# esc_shield.net
KiCad netlist of a schematic drawn in EAGLE
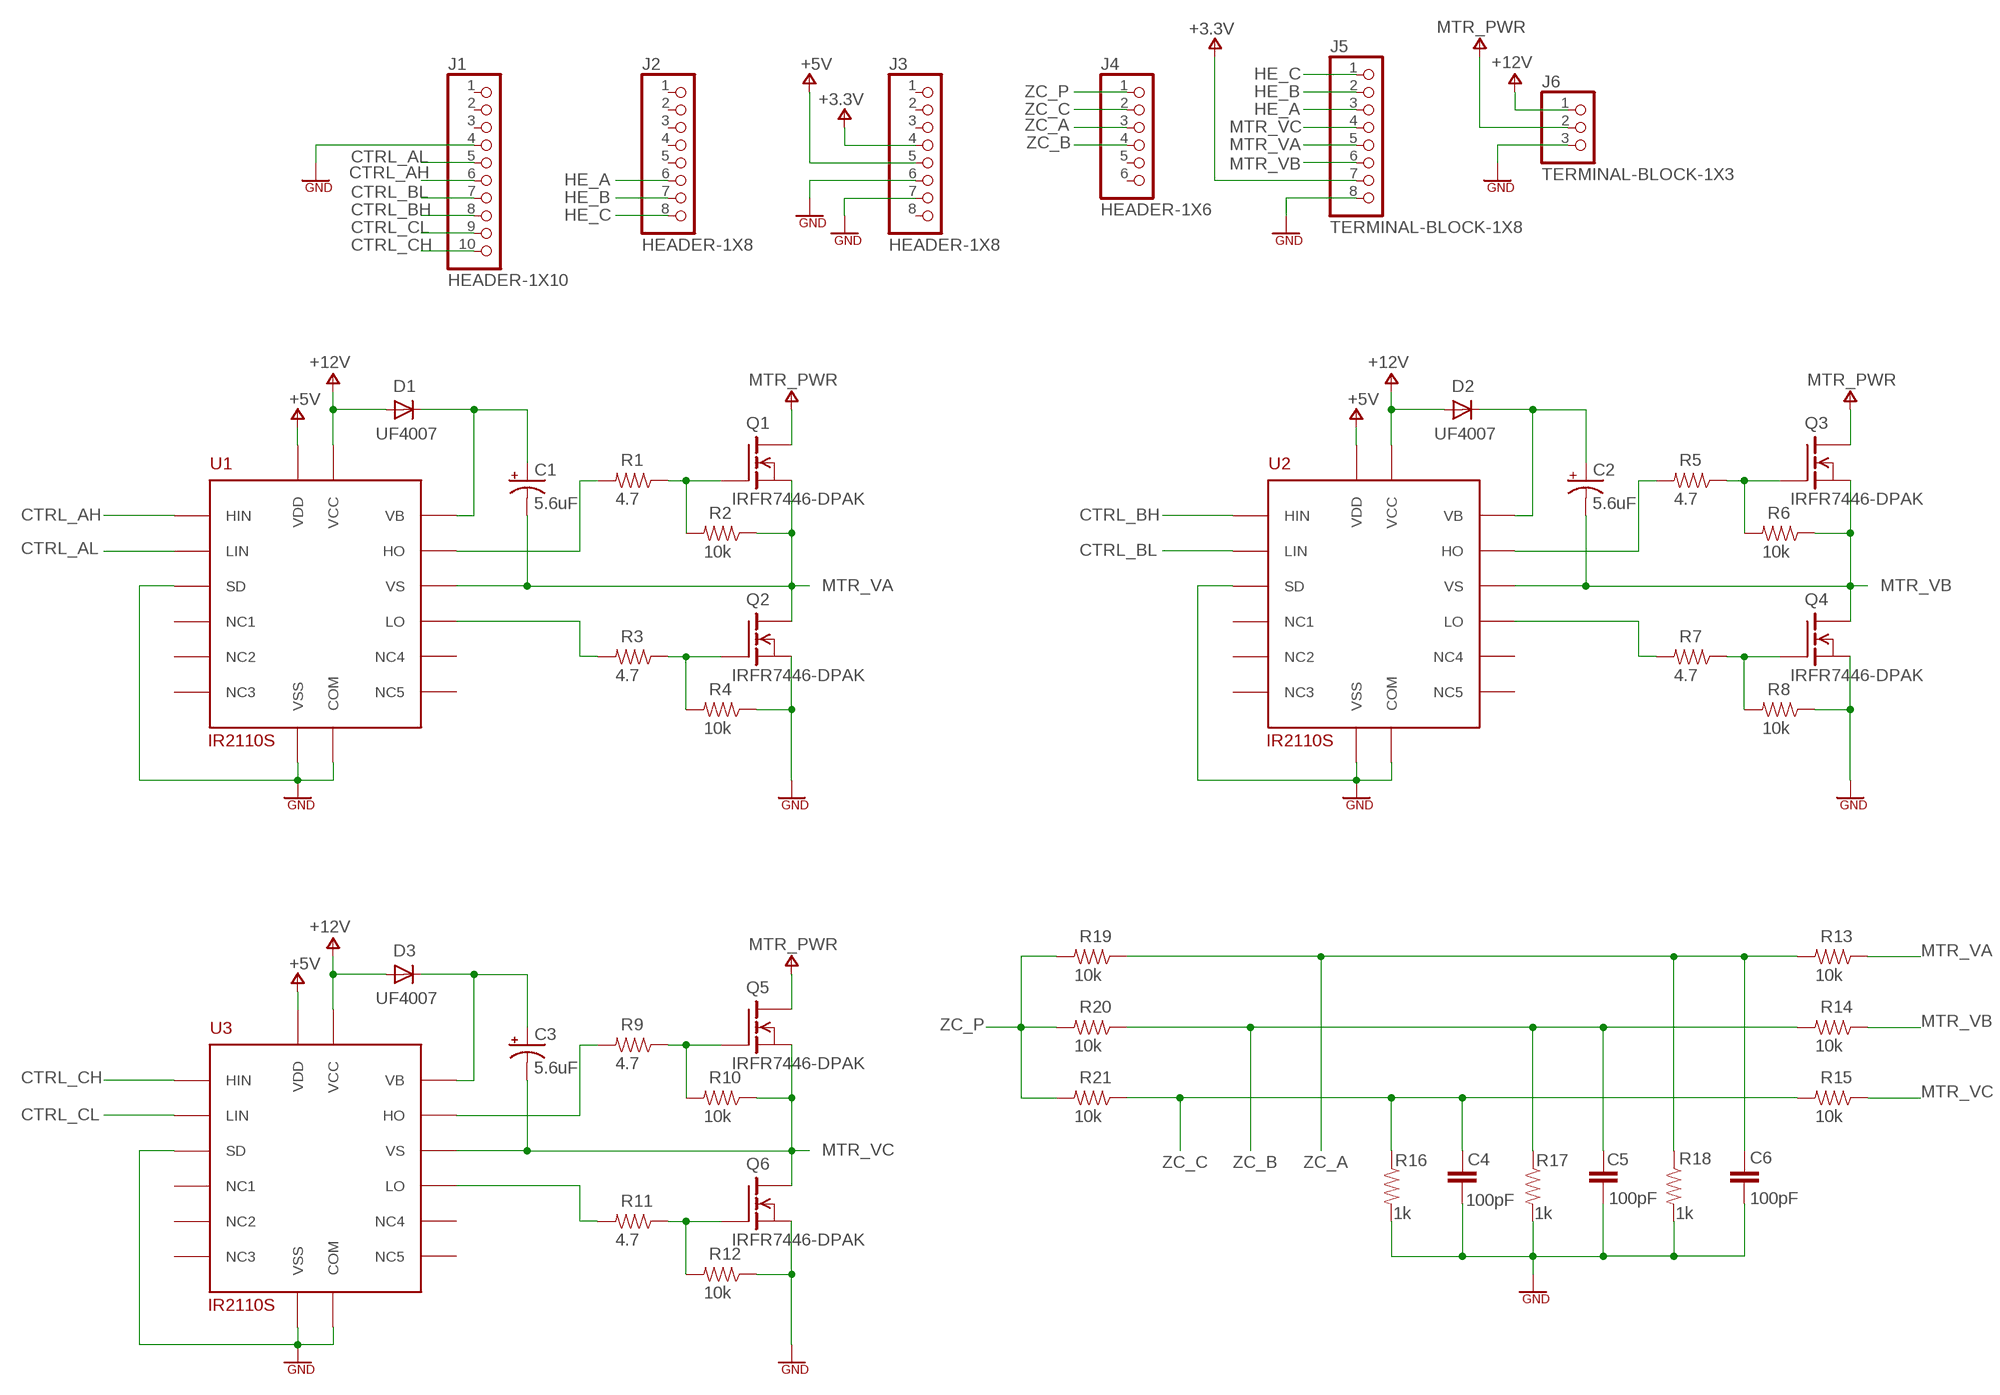
[diagram p0: schematic, sheet 1]

(export (version "E")
  (design (tool "Eeschema 10.0.6"))
  (components
    (comp (ref "C1")
      (value "5.6uF")
      (footprint "eagle-import:EIA7343-31")
      (libsource (lib "eagle-import") (part "CAP_TANT"))
    )
    (comp (ref "C2")
      (value "5.6uF")
      (footprint "eagle-import:EIA7343-31")
      (libsource (lib "eagle-import") (part "CAP_TANT"))
    )
    (comp (ref "C3")
      (value "5.6uF")
      (footprint "eagle-import:EIA7343-31")
      (libsource (lib "eagle-import") (part "CAP_TANT"))
    )
    (comp (ref "C4")
      (value "100pF")
      (footprint "eagle-import:SMD0603")
      (libsource (lib "eagle-import") (part "CAP_0603"))
    )
    (comp (ref "C5")
      (value "100pF")
      (footprint "eagle-import:SMD0603")
      (libsource (lib "eagle-import") (part "CAP_0603"))
    )
    (comp (ref "C6")
      (value "100pF")
      (footprint "eagle-import:SMD0603")
      (libsource (lib "eagle-import") (part "CAP_0603"))
    )
    (comp (ref "D1")
      (value "UF4007")
      (footprint "eagle-import:DO41-10")
      (libsource (lib "eagle-import") (part "UF4007"))
    )
    (comp (ref "D2")
      (value "UF4007")
      (footprint "eagle-import:DO41-10")
      (libsource (lib "eagle-import") (part "UF4007"))
    )
    (comp (ref "D3")
      (value "UF4007")
      (footprint "eagle-import:DO41-10")
      (libsource (lib "eagle-import") (part "UF4007"))
    )
    (comp (ref "J1")
      (value "HEADER-1X10")
      (footprint "eagle-import:1X10")
      (libsource (lib "eagle-import") (part "HEADER-1X10"))
    )
    (comp (ref "J2")
      (value "HEADER-1X8")
      (footprint "eagle-import:1X08")
      (libsource (lib "eagle-import") (part "HEADER-1X8"))
    )
    (comp (ref "J3")
      (value "HEADER-1X8")
      (footprint "eagle-import:1X08")
      (libsource (lib "eagle-import") (part "HEADER-1X8"))
    )
    (comp (ref "J4")
      (value "HEADER-1X6")
      (footprint "eagle-import:1X06")
      (libsource (lib "eagle-import") (part "HEADER-1X6"))
    )
    (comp (ref "J5")
      (value "TERMINAL-BLOCK-1X8")
      (footprint "eagle-import:1X08")
      (libsource (lib "eagle-import") (part "TERMINAL-BLOCK-1X8"))
    )
    (comp (ref "J6")
      (value "TERMINAL-BLOCK-1X3")
      (footprint "eagle-import:1X03")
      (libsource (lib "eagle-import") (part "TERMINAL-BLOCK-1X3"))
    )
    (comp (ref "Q1")
      (value "IRFR7446-DPAK")
      (footprint "eagle-import:TO252AA")
      (libsource (lib "eagle-import") (part "IRFR7446-DPAK"))
    )
    (comp (ref "Q2")
      (value "IRFR7446-DPAK")
      (footprint "eagle-import:TO252AA")
      (libsource (lib "eagle-import") (part "IRFR7446-DPAK"))
    )
    (comp (ref "Q3")
      (value "IRFR7446-DPAK")
      (footprint "eagle-import:TO252AA")
      (libsource (lib "eagle-import") (part "IRFR7446-DPAK"))
    )
    (comp (ref "Q4")
      (value "IRFR7446-DPAK")
      (footprint "eagle-import:TO252AA")
      (libsource (lib "eagle-import") (part "IRFR7446-DPAK"))
    )
    (comp (ref "Q5")
      (value "IRFR7446-DPAK")
      (footprint "eagle-import:TO252AA")
      (libsource (lib "eagle-import") (part "IRFR7446-DPAK"))
    )
    (comp (ref "Q6")
      (value "IRFR7446-DPAK")
      (footprint "eagle-import:TO252AA")
      (libsource (lib "eagle-import") (part "IRFR7446-DPAK"))
    )
    (comp (ref "R1")
      (value "4.7")
      (footprint "eagle-import:SMD0603")
      (libsource (lib "eagle-import") (part "RES_0603"))
    )
    (comp (ref "R2")
      (value "10k")
      (footprint "eagle-import:SMD0603")
      (libsource (lib "eagle-import") (part "RES_0603"))
    )
    (comp (ref "R3")
      (value "4.7")
      (footprint "eagle-import:SMD0603")
      (libsource (lib "eagle-import") (part "RES_0603"))
    )
    (comp (ref "R4")
      (value "10k")
      (footprint "eagle-import:SMD0603")
      (libsource (lib "eagle-import") (part "RES_0603"))
    )
    (comp (ref "R5")
      (value "4.7")
      (footprint "eagle-import:SMD0603")
      (libsource (lib "eagle-import") (part "RES_0603"))
    )
    (comp (ref "R6")
      (value "10k")
      (footprint "eagle-import:SMD0603")
      (libsource (lib "eagle-import") (part "RES_0603"))
    )
    (comp (ref "R7")
      (value "4.7")
      (footprint "eagle-import:SMD0603")
      (libsource (lib "eagle-import") (part "RES_0603"))
    )
    (comp (ref "R8")
      (value "10k")
      (footprint "eagle-import:SMD0603")
      (libsource (lib "eagle-import") (part "RES_0603"))
    )
    (comp (ref "R9")
      (value "4.7")
      (footprint "eagle-import:SMD0603")
      (libsource (lib "eagle-import") (part "RES_0603"))
    )
    (comp (ref "R10")
      (value "10k")
      (footprint "eagle-import:SMD0603")
      (libsource (lib "eagle-import") (part "RES_0603"))
    )
    (comp (ref "R11")
      (value "4.7")
      (footprint "eagle-import:SMD0603")
      (libsource (lib "eagle-import") (part "RES_0603"))
    )
    (comp (ref "R12")
      (value "10k")
      (footprint "eagle-import:SMD0603")
      (libsource (lib "eagle-import") (part "RES_0603"))
    )
    (comp (ref "R13")
      (value "10k")
      (footprint "eagle-import:SMD0603")
      (libsource (lib "eagle-import") (part "RES_0603"))
    )
    (comp (ref "R14")
      (value "10k")
      (footprint "eagle-import:SMD0603")
      (libsource (lib "eagle-import") (part "RES_0603"))
    )
    (comp (ref "R15")
      (value "10k")
      (footprint "eagle-import:SMD0603")
      (libsource (lib "eagle-import") (part "RES_0603"))
    )
    (comp (ref "R16")
      (value "1k")
      (footprint "eagle-import:SMD0603")
      (libsource (lib "eagle-import") (part "RES_0603"))
    )
    (comp (ref "R17")
      (value "1k")
      (footprint "eagle-import:SMD0603")
      (libsource (lib "eagle-import") (part "RES_0603"))
    )
    (comp (ref "R18")
      (value "1k")
      (footprint "eagle-import:SMD0603")
      (libsource (lib "eagle-import") (part "RES_0603"))
    )
    (comp (ref "R19")
      (value "10k")
      (footprint "eagle-import:SMD0603")
      (libsource (lib "eagle-import") (part "RES_0603"))
    )
    (comp (ref "R20")
      (value "10k")
      (footprint "eagle-import:SMD0603")
      (libsource (lib "eagle-import") (part "RES_0603"))
    )
    (comp (ref "R21")
      (value "10k")
      (footprint "eagle-import:SMD0603")
      (libsource (lib "eagle-import") (part "RES_0603"))
    )
    (comp (ref "U1")
      (value "IR2110S")
      (footprint "eagle-import:SO16L")
      (libsource (lib "eagle-import") (part "IR2110S"))
    )
    (comp (ref "U2")
      (value "IR2110S")
      (footprint "eagle-import:SO16L")
      (libsource (lib "eagle-import") (part "IR2110S"))
    )
    (comp (ref "U3")
      (value "IR2110S")
      (footprint "eagle-import:SO16L")
      (libsource (lib "eagle-import") (part "IR2110S"))
    )
  )
  (nets
    (net (code "1") (name "/CTRL_AH") (class "Default")
      (node (ref "J1") (pin "6") (pinfunction "6_6") (pintype "passive"))
      (node (ref "U1") (pin "12") (pinfunction "HIN_12") (pintype "input"))
    )
    (net (code "2") (name "/CTRL_AL") (class "Default")
      (node (ref "J1") (pin "5") (pinfunction "5_5") (pintype "passive"))
      (node (ref "U1") (pin "14") (pinfunction "LIN_14") (pintype "input"))
    )
    (net (code "3") (name "/CTRL_BH") (class "Default")
      (node (ref "J1") (pin "8") (pinfunction "8_8") (pintype "passive"))
      (node (ref "U2") (pin "12") (pinfunction "HIN_12") (pintype "input"))
    )
    (net (code "4") (name "/CTRL_BL") (class "Default")
      (node (ref "J1") (pin "7") (pinfunction "7_7") (pintype "passive"))
      (node (ref "U2") (pin "14") (pinfunction "LIN_14") (pintype "input"))
    )
    (net (code "5") (name "/CTRL_CH") (class "Default")
      (node (ref "J1") (pin "10") (pinfunction "10_10") (pintype "passive"))
      (node (ref "U3") (pin "12") (pinfunction "HIN_12") (pintype "input"))
    )
    (net (code "6") (name "/CTRL_CL") (class "Default")
      (node (ref "J1") (pin "9") (pinfunction "9_9") (pintype "passive"))
      (node (ref "U3") (pin "14") (pinfunction "LIN_14") (pintype "input"))
    )
    (net (code "7") (name "/HE_A") (class "Default")
      (node (ref "J2") (pin "6") (pinfunction "6_6") (pintype "passive"))
      (node (ref "J5") (pin "3") (pinfunction "3_3") (pintype "passive"))
    )
    (net (code "8") (name "/HE_B") (class "Default")
      (node (ref "J2") (pin "7") (pinfunction "7_7") (pintype "passive"))
      (node (ref "J5") (pin "2") (pinfunction "2_2") (pintype "passive"))
    )
    (net (code "9") (name "/HE_C") (class "Default")
      (node (ref "J2") (pin "8") (pinfunction "8_8") (pintype "passive"))
      (node (ref "J5") (pin "1") (pinfunction "1_1") (pintype "passive"))
    )
    (net (code "10") (name "/MTR_VA") (class "Default")
      (node (ref "C1") (pin "-") (pinfunction "-_-") (pintype "passive"))
      (node (ref "J5") (pin "5") (pinfunction "5_5") (pintype "passive"))
      (node (ref "Q1") (pin "3") (pinfunction "S_3") (pintype "passive"))
      (node (ref "Q2") (pin "4") (pinfunction "D_4") (pintype "passive"))
      (node (ref "R13") (pin "1") (pinfunction "1_1") (pintype "passive"))
      (node (ref "R2") (pin "1") (pinfunction "1_1") (pintype "passive"))
      (node (ref "U1") (pin "6") (pinfunction "VS_6") (pintype "output"))
    )
    (net (code "11") (name "/MTR_VB") (class "Default")
      (node (ref "C2") (pin "-") (pinfunction "-_-") (pintype "passive"))
      (node (ref "J5") (pin "6") (pinfunction "6_6") (pintype "passive"))
      (node (ref "Q3") (pin "3") (pinfunction "S_3") (pintype "passive"))
      (node (ref "Q4") (pin "4") (pinfunction "D_4") (pintype "passive"))
      (node (ref "R14") (pin "1") (pinfunction "1_1") (pintype "passive"))
      (node (ref "R6") (pin "1") (pinfunction "1_1") (pintype "passive"))
      (node (ref "U2") (pin "6") (pinfunction "VS_6") (pintype "output"))
    )
    (net (code "12") (name "/MTR_VC") (class "Default")
      (node (ref "C3") (pin "-") (pinfunction "-_-") (pintype "passive"))
      (node (ref "J5") (pin "4") (pinfunction "4_4") (pintype "passive"))
      (node (ref "Q5") (pin "3") (pinfunction "S_3") (pintype "passive"))
      (node (ref "Q6") (pin "4") (pinfunction "D_4") (pintype "passive"))
      (node (ref "R10") (pin "1") (pinfunction "1_1") (pintype "passive"))
      (node (ref "R15") (pin "1") (pinfunction "1_1") (pintype "passive"))
      (node (ref "U3") (pin "6") (pinfunction "VS_6") (pintype "output"))
    )
    (net (code "13") (name "/ZC_A") (class "Default")
      (node (ref "C6") (pin "1") (pinfunction "1_1") (pintype "passive"))
      (node (ref "J4") (pin "3") (pinfunction "3_3") (pintype "passive"))
      (node (ref "R13") (pin "2") (pinfunction "2_2") (pintype "passive"))
      (node (ref "R18") (pin "1") (pinfunction "1_1") (pintype "passive"))
      (node (ref "R19") (pin "1") (pinfunction "1_1") (pintype "passive"))
    )
    (net (code "14") (name "/ZC_B") (class "Default")
      (node (ref "C5") (pin "1") (pinfunction "1_1") (pintype "passive"))
      (node (ref "J4") (pin "4") (pinfunction "4_4") (pintype "passive"))
      (node (ref "R14") (pin "2") (pinfunction "2_2") (pintype "passive"))
      (node (ref "R17") (pin "1") (pinfunction "1_1") (pintype "passive"))
      (node (ref "R20") (pin "1") (pinfunction "1_1") (pintype "passive"))
    )
    (net (code "15") (name "/ZC_C") (class "Default")
      (node (ref "C4") (pin "1") (pinfunction "1_1") (pintype "passive"))
      (node (ref "J4") (pin "2") (pinfunction "2_2") (pintype "passive"))
      (node (ref "R15") (pin "2") (pinfunction "2_2") (pintype "passive"))
      (node (ref "R16") (pin "1") (pinfunction "1_1") (pintype "passive"))
      (node (ref "R21") (pin "1") (pinfunction "1_1") (pintype "passive"))
    )
    (net (code "16") (name "/ZC_P") (class "Default")
      (node (ref "J4") (pin "1") (pinfunction "1_1") (pintype "passive"))
      (node (ref "R19") (pin "2") (pinfunction "2_2") (pintype "passive"))
      (node (ref "R20") (pin "2") (pinfunction "2_2") (pintype "passive"))
      (node (ref "R21") (pin "2") (pinfunction "2_2") (pintype "passive"))
    )
    (net (code "17") (name "3V3SUP") (class "Default")
      (node (ref "J3") (pin "4") (pinfunction "4_4") (pintype "passive"))
      (node (ref "J5") (pin "7") (pinfunction "7_7") (pintype "passive"))
    )
    (net (code "18") (name "5VSUP") (class "Default")
      (node (ref "J3") (pin "5") (pinfunction "5_5") (pintype "passive"))
      (node (ref "U1") (pin "11") (pinfunction "VDD_11") (pintype "bidirectional"))
      (node (ref "U2") (pin "11") (pinfunction "VDD_11") (pintype "bidirectional"))
      (node (ref "U3") (pin "11") (pinfunction "VDD_11") (pintype "bidirectional"))
    )
    (net (code "19") (name "12VSUP") (class "Default")
      (node (ref "D1") (pin "A") (pinfunction "A_A") (pintype "passive"))
      (node (ref "D2") (pin "A") (pinfunction "A_A") (pintype "passive"))
      (node (ref "D3") (pin "A") (pinfunction "A_A") (pintype "passive"))
      (node (ref "J6") (pin "1") (pinfunction "1_1") (pintype "passive"))
      (node (ref "U1") (pin "3") (pinfunction "VCC_3") (pintype "bidirectional"))
      (node (ref "U2") (pin "3") (pinfunction "VCC_3") (pintype "bidirectional"))
      (node (ref "U3") (pin "3") (pinfunction "VCC_3") (pintype "bidirectional"))
    )
    (net (code "20") (name "GND") (class "Default")
      (node (ref "C4") (pin "2") (pinfunction "2_2") (pintype "passive"))
      (node (ref "C5") (pin "2") (pinfunction "2_2") (pintype "passive"))
      (node (ref "C6") (pin "2") (pinfunction "2_2") (pintype "passive"))
      (node (ref "J1") (pin "4") (pinfunction "4_4") (pintype "passive"))
      (node (ref "J3") (pin "6") (pinfunction "6_6") (pintype "passive"))
      (node (ref "J3") (pin "7") (pinfunction "7_7") (pintype "passive"))
      (node (ref "J5") (pin "8") (pinfunction "8_8") (pintype "passive"))
      (node (ref "J6") (pin "3") (pinfunction "3_3") (pintype "passive"))
      (node (ref "Q2") (pin "3") (pinfunction "S_3") (pintype "passive"))
      (node (ref "Q4") (pin "3") (pinfunction "S_3") (pintype "passive"))
      (node (ref "Q6") (pin "3") (pinfunction "S_3") (pintype "passive"))
      (node (ref "R12") (pin "1") (pinfunction "1_1") (pintype "passive"))
      (node (ref "R16") (pin "2") (pinfunction "2_2") (pintype "passive"))
      (node (ref "R17") (pin "2") (pinfunction "2_2") (pintype "passive"))
      (node (ref "R18") (pin "2") (pinfunction "2_2") (pintype "passive"))
      (node (ref "R4") (pin "1") (pinfunction "1_1") (pintype "passive"))
      (node (ref "R8") (pin "1") (pinfunction "1_1") (pintype "passive"))
      (node (ref "U1") (pin "13") (pinfunction "SD_13") (pintype "input"))
      (node (ref "U1") (pin "15") (pinfunction "VSS_15") (pintype "bidirectional"))
      (node (ref "U1") (pin "2") (pinfunction "COM_2") (pintype "bidirectional"))
      (node (ref "U2") (pin "13") (pinfunction "SD_13") (pintype "input"))
      (node (ref "U2") (pin "15") (pinfunction "VSS_15") (pintype "bidirectional"))
      (node (ref "U2") (pin "2") (pinfunction "COM_2") (pintype "bidirectional"))
      (node (ref "U3") (pin "13") (pinfunction "SD_13") (pintype "input"))
      (node (ref "U3") (pin "15") (pinfunction "VSS_15") (pintype "bidirectional"))
      (node (ref "U3") (pin "2") (pinfunction "COM_2") (pintype "bidirectional"))
    )
    (net (code "21") (name "MTR_PWR") (class "Default")
      (node (ref "J6") (pin "2") (pinfunction "2_2") (pintype "passive"))
      (node (ref "Q1") (pin "4") (pinfunction "D_4") (pintype "passive"))
      (node (ref "Q3") (pin "4") (pinfunction "D_4") (pintype "passive"))
      (node (ref "Q5") (pin "4") (pinfunction "D_4") (pintype "passive"))
    )
    (net (code "22") (name "Net-(Q1-G)") (class "Default")
      (node (ref "Q1") (pin "1") (pinfunction "G_1") (pintype "passive"))
      (node (ref "R1") (pin "1") (pinfunction "1_1") (pintype "passive"))
      (node (ref "R2") (pin "2") (pinfunction "2_2") (pintype "passive"))
    )
    (net (code "23") (name "Net-(Q2-G)") (class "Default")
      (node (ref "Q2") (pin "1") (pinfunction "G_1") (pintype "passive"))
      (node (ref "R3") (pin "1") (pinfunction "1_1") (pintype "passive"))
      (node (ref "R4") (pin "2") (pinfunction "2_2") (pintype "passive"))
    )
    (net (code "24") (name "Net-(Q3-G)") (class "Default")
      (node (ref "Q3") (pin "1") (pinfunction "G_1") (pintype "passive"))
      (node (ref "R5") (pin "1") (pinfunction "1_1") (pintype "passive"))
      (node (ref "R6") (pin "2") (pinfunction "2_2") (pintype "passive"))
    )
    (net (code "25") (name "Net-(Q4-G)") (class "Default")
      (node (ref "Q4") (pin "1") (pinfunction "G_1") (pintype "passive"))
      (node (ref "R7") (pin "1") (pinfunction "1_1") (pintype "passive"))
      (node (ref "R8") (pin "2") (pinfunction "2_2") (pintype "passive"))
    )
    (net (code "26") (name "Net-(Q5-G)") (class "Default")
      (node (ref "Q5") (pin "1") (pinfunction "G_1") (pintype "passive"))
      (node (ref "R10") (pin "2") (pinfunction "2_2") (pintype "passive"))
      (node (ref "R9") (pin "1") (pinfunction "1_1") (pintype "passive"))
    )
    (net (code "27") (name "Net-(Q6-G)") (class "Default")
      (node (ref "Q6") (pin "1") (pinfunction "G_1") (pintype "passive"))
      (node (ref "R11") (pin "1") (pinfunction "1_1") (pintype "passive"))
      (node (ref "R12") (pin "2") (pinfunction "2_2") (pintype "passive"))
    )
    (net (code "28") (name "Net-(U1-HO)") (class "Default")
      (node (ref "R1") (pin "2") (pinfunction "2_2") (pintype "passive"))
      (node (ref "U1") (pin "8") (pinfunction "HO_8") (pintype "output"))
    )
    (net (code "29") (name "Net-(U1-LO)") (class "Default")
      (node (ref "R3") (pin "2") (pinfunction "2_2") (pintype "passive"))
      (node (ref "U1") (pin "1") (pinfunction "LO_1") (pintype "output"))
    )
    (net (code "30") (name "Net-(U1-VB)") (class "Default")
      (node (ref "C1") (pin "+") (pinfunction "+_+") (pintype "passive"))
      (node (ref "D1") (pin "C") (pinfunction "C_C") (pintype "passive"))
      (node (ref "U1") (pin "7") (pinfunction "VB_7") (pintype "output"))
    )
    (net (code "31") (name "Net-(U2-HO)") (class "Default")
      (node (ref "R5") (pin "2") (pinfunction "2_2") (pintype "passive"))
      (node (ref "U2") (pin "8") (pinfunction "HO_8") (pintype "output"))
    )
    (net (code "32") (name "Net-(U2-LO)") (class "Default")
      (node (ref "R7") (pin "2") (pinfunction "2_2") (pintype "passive"))
      (node (ref "U2") (pin "1") (pinfunction "LO_1") (pintype "output"))
    )
    (net (code "33") (name "Net-(U2-VB)") (class "Default")
      (node (ref "C2") (pin "+") (pinfunction "+_+") (pintype "passive"))
      (node (ref "D2") (pin "C") (pinfunction "C_C") (pintype "passive"))
      (node (ref "U2") (pin "7") (pinfunction "VB_7") (pintype "output"))
    )
    (net (code "34") (name "Net-(U3-HO)") (class "Default")
      (node (ref "R9") (pin "2") (pinfunction "2_2") (pintype "passive"))
      (node (ref "U3") (pin "8") (pinfunction "HO_8") (pintype "output"))
    )
    (net (code "35") (name "Net-(U3-LO)") (class "Default")
      (node (ref "R11") (pin "2") (pinfunction "2_2") (pintype "passive"))
      (node (ref "U3") (pin "1") (pinfunction "LO_1") (pintype "output"))
    )
    (net (code "36") (name "Net-(U3-VB)") (class "Default")
      (node (ref "C3") (pin "+") (pinfunction "+_+") (pintype "passive"))
      (node (ref "D3") (pin "C") (pinfunction "C_C") (pintype "passive"))
      (node (ref "U3") (pin "7") (pinfunction "VB_7") (pintype "output"))
    )
    (net (code "37") (name "unconnected-(J1-Pad1)") (class "Default")
      (node (ref "J1") (pin "1") (pinfunction "1_1") (pintype "passive"))
    )
    (net (code "38") (name "unconnected-(J1-Pad2)") (class "Default")
      (node (ref "J1") (pin "2") (pinfunction "2_2") (pintype "passive"))
    )
    (net (code "39") (name "unconnected-(J1-Pad3)") (class "Default")
      (node (ref "J1") (pin "3") (pinfunction "3_3") (pintype "passive"))
    )
    (net (code "40") (name "unconnected-(J2-Pad1)") (class "Default")
      (node (ref "J2") (pin "1") (pinfunction "1_1") (pintype "passive"))
    )
    (net (code "41") (name "unconnected-(J2-Pad2)") (class "Default")
      (node (ref "J2") (pin "2") (pinfunction "2_2") (pintype "passive"))
    )
    (net (code "42") (name "unconnected-(J2-Pad3)") (class "Default")
      (node (ref "J2") (pin "3") (pinfunction "3_3") (pintype "passive"))
    )
    (net (code "43") (name "unconnected-(J2-Pad4)") (class "Default")
      (node (ref "J2") (pin "4") (pinfunction "4_4") (pintype "passive"))
    )
    (net (code "44") (name "unconnected-(J2-Pad5)") (class "Default")
      (node (ref "J2") (pin "5") (pinfunction "5_5") (pintype "passive"))
    )
    (net (code "45") (name "unconnected-(J3-Pad1)") (class "Default")
      (node (ref "J3") (pin "1") (pinfunction "1_1") (pintype "passive"))
    )
    (net (code "46") (name "unconnected-(J3-Pad2)") (class "Default")
      (node (ref "J3") (pin "2") (pinfunction "2_2") (pintype "passive"))
    )
    (net (code "47") (name "unconnected-(J3-Pad3)") (class "Default")
      (node (ref "J3") (pin "3") (pinfunction "3_3") (pintype "passive"))
    )
    (net (code "48") (name "unconnected-(J3-Pad8)") (class "Default")
      (node (ref "J3") (pin "8") (pinfunction "8_8") (pintype "passive"))
    )
    (net (code "49") (name "unconnected-(J4-Pad5)") (class "Default")
      (node (ref "J4") (pin "5") (pinfunction "5_5") (pintype "passive"))
    )
    (net (code "50") (name "unconnected-(J4-Pad6)") (class "Default")
      (node (ref "J4") (pin "6") (pinfunction "6_6") (pintype "passive"))
    )
    (net (code "51") (name "unconnected-(U1-NC1-Pad4)") (class "Default")
      (node (ref "U1") (pin "4") (pinfunction "NC1_4") (pintype "no_connect"))
    )
    (net (code "52") (name "unconnected-(U1-NC2-Pad5)") (class "Default")
      (node (ref "U1") (pin "5") (pinfunction "NC2_5") (pintype "no_connect"))
    )
    (net (code "53") (name "unconnected-(U1-NC3-Pad9)") (class "Default")
      (node (ref "U1") (pin "9") (pinfunction "NC3_9") (pintype "no_connect"))
    )
    (net (code "54") (name "unconnected-(U1-NC4-Pad10)") (class "Default")
      (node (ref "U1") (pin "10") (pinfunction "NC4_10") (pintype "no_connect"))
    )
    (net (code "55") (name "unconnected-(U1-NC5-Pad16)") (class "Default")
      (node (ref "U1") (pin "16") (pinfunction "NC5_16") (pintype "no_connect"))
    )
    (net (code "56") (name "unconnected-(U2-NC1-Pad4)") (class "Default")
      (node (ref "U2") (pin "4") (pinfunction "NC1_4") (pintype "no_connect"))
    )
    (net (code "57") (name "unconnected-(U2-NC2-Pad5)") (class "Default")
      (node (ref "U2") (pin "5") (pinfunction "NC2_5") (pintype "no_connect"))
    )
    (net (code "58") (name "unconnected-(U2-NC3-Pad9)") (class "Default")
      (node (ref "U2") (pin "9") (pinfunction "NC3_9") (pintype "no_connect"))
    )
    (net (code "59") (name "unconnected-(U2-NC4-Pad10)") (class "Default")
      (node (ref "U2") (pin "10") (pinfunction "NC4_10") (pintype "no_connect"))
    )
    (net (code "60") (name "unconnected-(U2-NC5-Pad16)") (class "Default")
      (node (ref "U2") (pin "16") (pinfunction "NC5_16") (pintype "no_connect"))
    )
    (net (code "61") (name "unconnected-(U3-NC1-Pad4)") (class "Default")
      (node (ref "U3") (pin "4") (pinfunction "NC1_4") (pintype "no_connect"))
    )
    (net (code "62") (name "unconnected-(U3-NC2-Pad5)") (class "Default")
      (node (ref "U3") (pin "5") (pinfunction "NC2_5") (pintype "no_connect"))
    )
    (net (code "63") (name "unconnected-(U3-NC3-Pad9)") (class "Default")
      (node (ref "U3") (pin "9") (pinfunction "NC3_9") (pintype "no_connect"))
    )
    (net (code "64") (name "unconnected-(U3-NC4-Pad10)") (class "Default")
      (node (ref "U3") (pin "10") (pinfunction "NC4_10") (pintype "no_connect"))
    )
    (net (code "65") (name "unconnected-(U3-NC5-Pad16)") (class "Default")
      (node (ref "U3") (pin "16") (pinfunction "NC5_16") (pintype "no_connect"))
    )
  )
)
